# Sheet1.net
KiCad netlist of a schematic drawn in Altium Designer
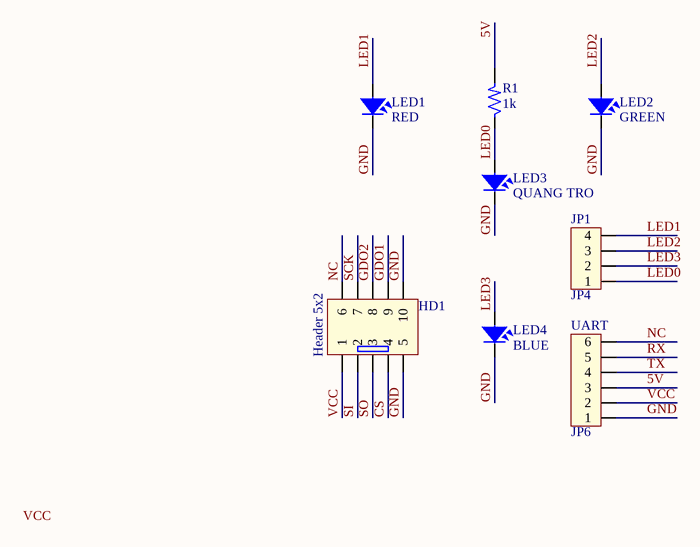
[diagram p0: Sheet1.SchDoc]

(export (version "E")
  (design (tool "Eeschema 10.0.6"))
  (components
    (comp (ref "HD1")
      (value "Header 5x2")
      (footprint "HED2X5_cen")
      (libsource (lib "syhaunguyen") (part "HED5x2"))
    )
    (comp (ref "JP1")
      (value "JP4")
      (footprint "CON4")
      (description "Connector 4")
      (libsource (lib "syhaunguyen") (part "Con4"))
    )
    (comp (ref "LED1")
      (value "RED")
      (footprint "LED_5mm")
      (description "LED Single colour Green and Red")
      (libsource (lib "syhaunguyen") (part "LED"))
    )
    (comp (ref "LED2")
      (value "GREEN")
      (footprint "LED_5mm")
      (description "LED Single colour Green and Red")
      (libsource (lib "syhaunguyen") (part "LED"))
    )
    (comp (ref "LED3")
      (value "QUANG TRO")
      (footprint "LED_5mm")
      (description "LED Single colour Green and Red")
      (libsource (lib "syhaunguyen") (part "LED"))
    )
    (comp (ref "LED4")
      (value "BLUE")
      (footprint "LED_5mm")
      (description "LED Single colour Green and Red")
      (libsource (lib "syhaunguyen") (part "LED"))
    )
    (comp (ref "R1")
      (value "1k")
      (footprint "R1/2W")
      (description "Resistor 1/4W")
      (libsource (lib "syhaunguyen") (part "R"))
    )
    (comp (ref "UART")
      (value "JP6")
      (footprint "CON6")
      (description "Connector 6")
      (libsource (lib "syhaunguyen") (part "Con6"))
    )
  )
  (nets
    (net (code "1") (name "/5V") (class "Default")
      (node (ref "R1") (pin "2") (pinfunction "2_2") (pintype "passive"))
      (node (ref "UART") (pin "3") (pinfunction "3_3") (pintype "passive"))
    )
    (net (code "2") (name "/CS") (class "Default")
      (node (ref "HD1") (pin "4") (pinfunction "4_4") (pintype "passive"))
    )
    (net (code "3") (name "/GDO1") (class "Default")
      (node (ref "HD1") (pin "9") (pinfunction "9_9") (pintype "passive"))
    )
    (net (code "4") (name "/GDO2") (class "Default")
      (node (ref "HD1") (pin "8") (pinfunction "8_8") (pintype "passive"))
    )
    (net (code "5") (name "/GND") (class "Default")
      (node (ref "HD1") (pin "10") (pinfunction "10_10") (pintype "passive"))
      (node (ref "HD1") (pin "5") (pinfunction "5_5") (pintype "passive"))
      (node (ref "LED1") (pin "2") (pinfunction "2_2") (pintype "passive"))
      (node (ref "LED2") (pin "2") (pinfunction "2_2") (pintype "passive"))
      (node (ref "LED3") (pin "2") (pinfunction "2_2") (pintype "passive"))
      (node (ref "LED4") (pin "2") (pinfunction "2_2") (pintype "passive"))
      (node (ref "UART") (pin "1") (pinfunction "1_1") (pintype "passive"))
    )
    (net (code "6") (name "/LED0") (class "Default")
      (node (ref "JP1") (pin "1") (pinfunction "1_1") (pintype "passive"))
      (node (ref "LED3") (pin "1") (pinfunction "1_1") (pintype "passive"))
      (node (ref "R1") (pin "1") (pinfunction "1_1") (pintype "passive"))
    )
    (net (code "7") (name "/LED1") (class "Default")
      (node (ref "JP1") (pin "4") (pinfunction "4_4") (pintype "passive"))
      (node (ref "LED1") (pin "1") (pinfunction "1_1") (pintype "passive"))
    )
    (net (code "8") (name "/LED2") (class "Default")
      (node (ref "JP1") (pin "3") (pinfunction "3_3") (pintype "passive"))
      (node (ref "LED2") (pin "1") (pinfunction "1_1") (pintype "passive"))
    )
    (net (code "9") (name "/LED3") (class "Default")
      (node (ref "JP1") (pin "2") (pinfunction "2_2") (pintype "passive"))
      (node (ref "LED4") (pin "1") (pinfunction "1_1") (pintype "passive"))
    )
    (net (code "10") (name "/NC") (class "Default")
      (node (ref "HD1") (pin "6") (pinfunction "6_6") (pintype "passive"))
      (node (ref "UART") (pin "6") (pinfunction "6_6") (pintype "passive"))
    )
    (net (code "11") (name "/RX") (class "Default")
      (node (ref "UART") (pin "5") (pinfunction "5_5") (pintype "passive"))
    )
    (net (code "12") (name "/SCK") (class "Default")
      (node (ref "HD1") (pin "7") (pinfunction "7_7") (pintype "passive"))
    )
    (net (code "13") (name "/SI") (class "Default")
      (node (ref "HD1") (pin "2") (pinfunction "2_2") (pintype "passive"))
    )
    (net (code "14") (name "/SO") (class "Default")
      (node (ref "HD1") (pin "3") (pinfunction "3_3") (pintype "passive"))
    )
    (net (code "15") (name "/TX") (class "Default")
      (node (ref "UART") (pin "4") (pinfunction "4_4") (pintype "passive"))
    )
    (net (code "16") (name "/VCC") (class "Default")
      (node (ref "HD1") (pin "1") (pinfunction "1_1") (pintype "passive"))
      (node (ref "UART") (pin "2") (pinfunction "2_2") (pintype "passive"))
    )
  )
)
